# schematic.net
KiCad netlist of a schematic drawn in Altium Designer
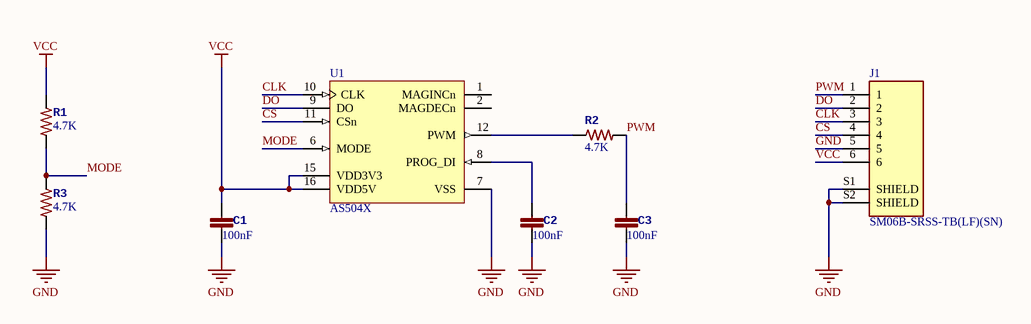
[diagram p0: schematic.SchDoc]

(export (version "E")
  (design (tool "Eeschema 10.0.6"))
  (components
    (comp (ref "C1")
      (value "100nF")
      (footprint "_0805")
      (fields (field (name "Comment") "Cap"))
      (libsource (lib "Passives_Integrated_Library") (part "Cap_1"))
    )
    (comp (ref "C2")
      (value "100nF")
      (footprint "_0805")
      (fields (field (name "Comment") "Cap"))
      (libsource (lib "Passives_Integrated_Library") (part "Cap_1"))
    )
    (comp (ref "C3")
      (value "100nF")
      (footprint "_0805")
      (fields (field (name "Comment") "Cap"))
      (libsource (lib "Passives_Integrated_Library") (part "Cap_1"))
    )
    (comp (ref "J1")
      (value "SM06B-SRSS-TB(LF)(SN)")
      (footprint "JST_SM06B-SRSS-TB(LF)(SN)")
      (description "Connector Header Surface Mount, Right Angle 6 position 0.039 _1.00mm_")
      (fields
        (field (name "MP") "SM06B-SRSS-TB_LF__SN_")
        (field (name "DIGI-KEY_PART_NUMBER") "455-1806-1-ND")
      )
      (libsource (lib "SM06B-SRSS-TB_LF__SN_") (part "SM06B-SRSS-TB(LF)(SN)"))
    )
    (comp (ref "R1")
      (value "4.7K")
      (footprint "_0805")
      (fields (field (name "Comment") "Resistor"))
      (libsource (lib "Passives_Integrated_Library") (part "Resistor"))
    )
    (comp (ref "R2")
      (value "4.7K")
      (footprint "_0805")
      (fields (field (name "Comment") "Resistor"))
      (libsource (lib "Passives_Integrated_Library") (part "Resistor"))
    )
    (comp (ref "R3")
      (value "4.7K")
      (footprint "_0805")
      (fields (field (name "Comment") "Resistor"))
      (libsource (lib "Passives_Integrated_Library") (part "Resistor"))
    )
    (comp (ref "U1")
      (value "AS504X")
      (footprint "AS504X")
      (libsource (lib "Sensors_Integrated_Library") (part "AS504X"))
    )
  )
  (nets
    (net (code "1") (name "/CLK") (class "Default")
      (node (ref "J1") (pin "3") (pinfunction "3_3") (pintype "passive"))
      (node (ref "U1") (pin "10") (pinfunction "CLK_10") (pintype "input"))
    )
    (net (code "2") (name "/CS") (class "Default")
      (node (ref "J1") (pin "4") (pinfunction "4_4") (pintype "passive"))
      (node (ref "U1") (pin "11") (pinfunction "CSn_11") (pintype "input"))
    )
    (net (code "3") (name "/DO") (class "Default")
      (node (ref "J1") (pin "2") (pinfunction "2_2") (pintype "passive"))
      (node (ref "U1") (pin "9") (pinfunction "DO_9") (pintype "tri_state"))
    )
    (net (code "4") (name "/MODE") (class "Default")
      (node (ref "R1") (pin "2") (pinfunction "2_2") (pintype "passive"))
      (node (ref "R3") (pin "1") (pinfunction "1_1") (pintype "passive"))
      (node (ref "U1") (pin "6") (pinfunction "MODE_6") (pintype "input"))
    )
    (net (code "5") (name "/PWM") (class "Default")
      (node (ref "C3") (pin "1") (pinfunction "1_1") (pintype "passive"))
      (node (ref "J1") (pin "1") (pinfunction "1_1") (pintype "passive"))
      (node (ref "R2") (pin "2") (pinfunction "2_2") (pintype "passive"))
    )
    (net (code "6") (name "GND") (class "Default")
      (node (ref "C1") (pin "2") (pinfunction "2_2") (pintype "passive"))
      (node (ref "C2") (pin "2") (pinfunction "2_2") (pintype "passive"))
      (node (ref "C3") (pin "2") (pinfunction "2_2") (pintype "passive"))
      (node (ref "J1") (pin "5") (pinfunction "5_5") (pintype "passive"))
      (node (ref "J1") (pin "S1") (pinfunction "SHIELD_S1") (pintype "passive"))
      (node (ref "J1") (pin "S2") (pinfunction "SHIELD_S2") (pintype "passive"))
      (node (ref "R3") (pin "2") (pinfunction "2_2") (pintype "passive"))
      (node (ref "U1") (pin "7") (pinfunction "VSS_7") (pintype "power_in"))
    )
    (net (code "7") (name "Net-(U1-PROG_DI)") (class "Default")
      (node (ref "C2") (pin "1") (pinfunction "1_1") (pintype "passive"))
      (node (ref "U1") (pin "8") (pinfunction "PROG_DI_8") (pintype "input"))
    )
    (net (code "8") (name "Net-(U1-PWM)") (class "Default")
      (node (ref "R2") (pin "1") (pinfunction "1_1") (pintype "passive"))
      (node (ref "U1") (pin "12") (pinfunction "PWM_12") (pintype "output"))
    )
    (net (code "9") (name "VCC") (class "Default")
      (node (ref "C1") (pin "1") (pinfunction "1_1") (pintype "passive"))
      (node (ref "J1") (pin "6") (pinfunction "6_6") (pintype "passive"))
      (node (ref "R1") (pin "1") (pinfunction "1_1") (pintype "passive"))
      (node (ref "U1") (pin "15") (pinfunction "VDD3V3_15") (pintype "power_in"))
      (node (ref "U1") (pin "16") (pinfunction "VDD5V_16") (pintype "power_in"))
    )
    (net (code "10") (name "unconnected-(U1-MAGDECn-Pad2)") (class "Default")
      (node (ref "U1") (pin "2") (pinfunction "MAGDECn_2") (pintype "open_collector"))
    )
    (net (code "11") (name "unconnected-(U1-MAGINCn-Pad1)") (class "Default")
      (node (ref "U1") (pin "1") (pinfunction "MAGINCn_1") (pintype "open_collector"))
    )
  )
)
